# cape.net
KiCad netlist of a schematic drawn in Altium Designer
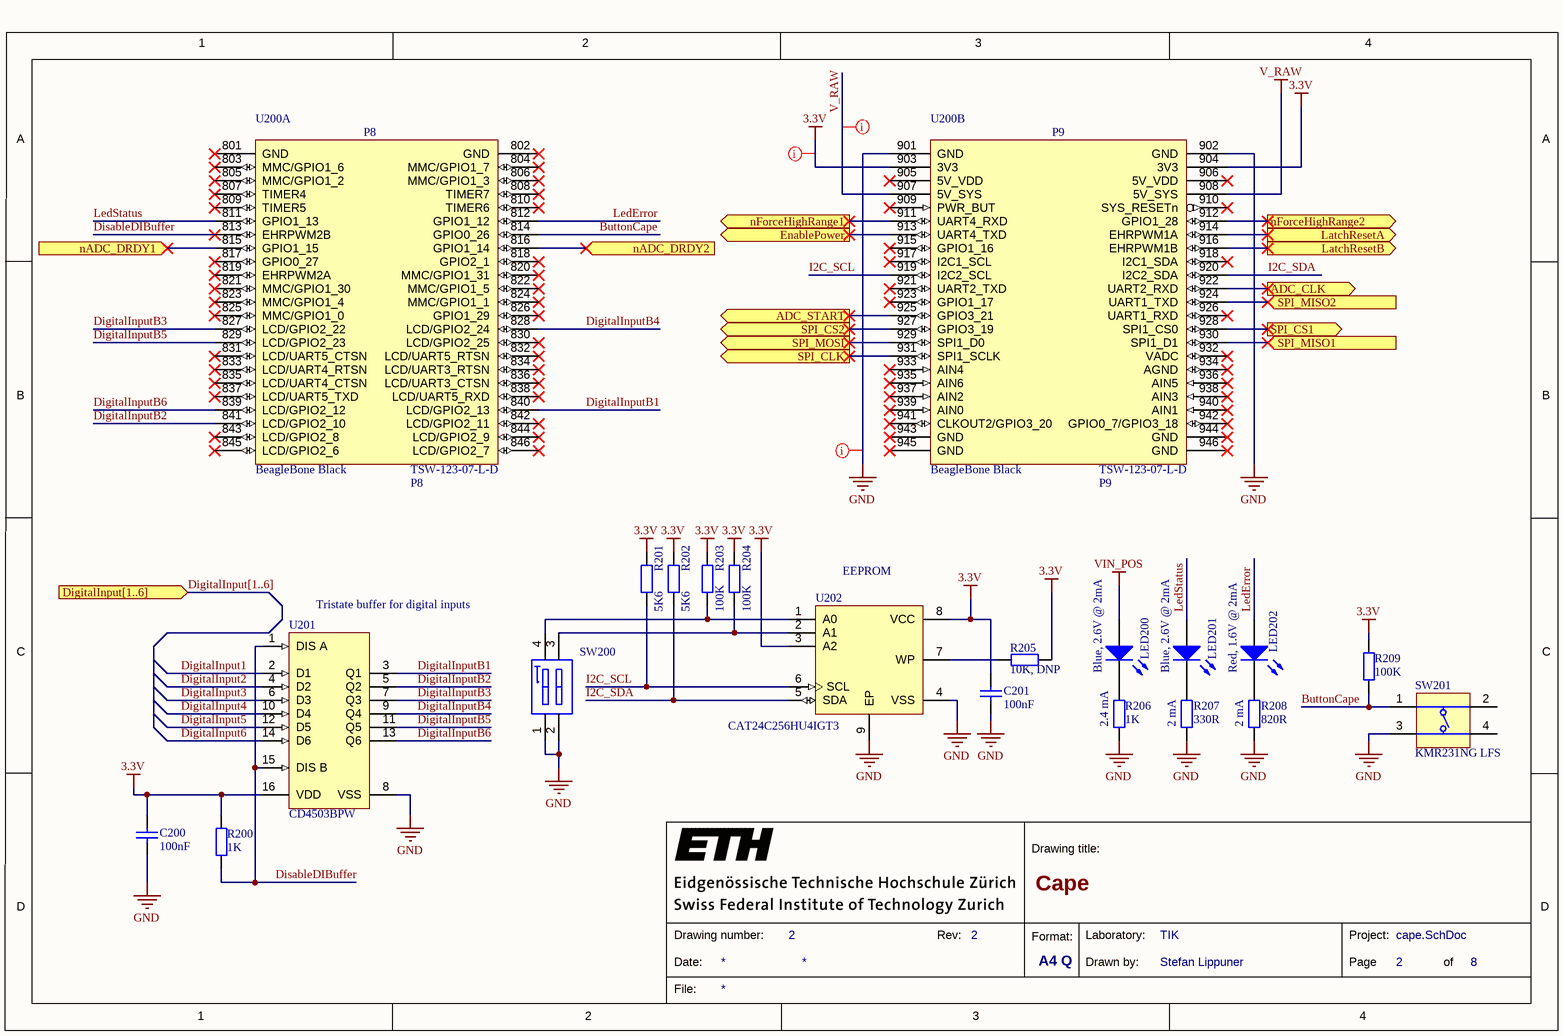
[diagram p0: cape.SchDoc]

(export (version "E")
  (design (tool "Eeschema 10.0.6"))
  (components
    (comp (ref "C200")
      (value "100nF")
      (footprint "CAPC0402(1005)60_L")
      (description "CAP 100nF 16V -20% to +80% 0402 (1005 Metric) Thickness 0.6mm SMD")
      (fields (field (name "TOLERANCE") "-20% to +80%"))
      (libsource (lib "Altium Content Vault") (part "CMP-1034-02071-1"))
    )
    (comp (ref "C201")
      (value "100nF")
      (footprint "CAPC0402(1005)60_L")
      (description "CAP 100nF 16V -20% to +80% 0402 (1005 Metric) Thickness 0.6mm SMD")
      (fields (field (name "TOLERANCE") "-20% to +80%"))
      (libsource (lib "Altium Content Vault") (part "CMP-1034-02071-1"))
    )
    (comp (ref "LED200")
      (value "Blue, 2.6V @ 2mA")
      (footprint "0603_A")
      (description "SMD mono-color Chip LED, WL-SMCW, Blue")
      (fields (field (name "PARTNUMBER") "150060BS75000") (field (name "MANUFACTURER") "Wuerth Elektronik"))
      (libsource (lib "Altium Content Vault") (part "CMP-1426-00003-1"))
    )
    (comp (ref "LED201")
      (value "Blue, 2.6V @ 2mA")
      (footprint "0603_A")
      (description "SMD mono-color Chip LED, WL-SMCW, Blue")
      (fields (field (name "PARTNUMBER") "150060BS75000") (field (name "MANUFACTURER") "Wuerth Elektronik"))
      (libsource (lib "Altium Content Vault") (part "CMP-1426-00003-1"))
    )
    (comp (ref "LED202")
      (value "Red, 1.6V @ 2mA")
      (footprint "0603_A")
      (description "SMD mono-color Chip LED, WL-SMCW, Red")
      (fields (field (name "MANUFACTURER") "Wuerth Elektronik") (field (name "PARTNUMBER") "150060RS75000"))
      (libsource (lib "Altium Content Vault") (part "WE-LED_K1A2-2"))
    )
    (comp (ref "P8")
      (value "TSW-123-07-L-D (BOM)")
      (description "Conn Unshrouded Header HDR 46 POS 2.54mm Solder ST Thru-Hole")
      (libsource (lib "TSW-123-07-L-D") (part "TSW-123-07-L-D (BOM)"))
    )
    (comp (ref "P9")
      (value "TSW-123-07-L-D (BOM)")
      (description "Conn Unshrouded Header HDR 46 POS 2.54mm Solder ST Thru-Hole")
      (libsource (lib "TSW-123-07-L-D") (part "TSW-123-07-L-D (BOM)"))
    )
    (comp (ref "R200")
      (value "1K")
      (footprint "RESC0402(1005)_L")
      (description "1K 0.063W 1% 0402 (1005 Metric)  SMD")
      (fields (field (name "TOLERANCE") "1 %") (field (name "POWER") "0.063 W"))
      (libsource (lib "Altium Content Vault") (part "RES"))
    )
    (comp (ref "R201")
      (value "5K6")
      (footprint "RESC0402(1005)_L")
      (description "5K6 0.063W 5% 0402 (1005 Metric)  SMD")
      (fields (field (name "TOLERANCE") "5 %") (field (name "POWER") "0.063 W"))
      (libsource (lib "Altium Content Vault") (part "CMP-1011-00092-1"))
    )
    (comp (ref "R202")
      (value "5K6")
      (footprint "RESC0402(1005)_L")
      (description "5K6 0.063W 5% 0402 (1005 Metric)  SMD")
      (fields (field (name "TOLERANCE") "5 %") (field (name "POWER") "0.063 W"))
      (libsource (lib "Altium Content Vault") (part "CMP-1011-00092-1"))
    )
    (comp (ref "R203")
      (value "100K")
      (footprint "RESC0402(1005)_L")
      (description "100K 0.063W 1% 0402 (1005 Metric)  SMD")
      (fields (field (name "POWER") "0.063 W") (field (name "TOLERANCE") "1 %"))
      (libsource (lib "Altium Content Vault") (part "CMP-1011-00736"))
    )
    (comp (ref "R204")
      (value "100K")
      (footprint "RESC0402(1005)_L")
      (description "100K 0.063W 1% 0402 (1005 Metric)  SMD")
      (fields (field (name "POWER") "0.063 W") (field (name "TOLERANCE") "1 %"))
      (libsource (lib "Altium Content Vault") (part "CMP-1011-00736"))
    )
    (comp (ref "R205")
      (value "10K, DNP")
      (footprint "RESC0402(1005)_L")
      (description "10K 0.063W 1% 0402 (1005 Metric)  SMD")
      (fields (field (name "TOLERANCE") "1 %") (field (name "POWER") "0.063 W"))
      (libsource (lib "Altium Content Vault") (part "CMP-1011-00623-1"))
    )
    (comp (ref "R206")
      (value "1K")
      (footprint "RESC0402(1005)_L")
      (description "1K 0.063W 1% 0402 (1005 Metric)  SMD")
      (fields (field (name "TOLERANCE") "1 %") (field (name "POWER") "0.063 W"))
      (libsource (lib "Altium Content Vault") (part "RES"))
    )
    (comp (ref "R207")
      (value "330R")
      (footprint "RESC0402(1005)_L")
      (description "330R 0.063W 5% 0402 (1005 Metric)  SMD")
      (fields (field (name "TOLERANCE") "5 %") (field (name "POWER") "0.063 W"))
      (libsource (lib "Altium Content Vault") (part "CMP-1011-00062-1"))
    )
    (comp (ref "R208")
      (value "820R")
      (footprint "RESC0402(1005)_L")
      (description "820R 0.063W 5% 0402 (1005 Metric)  SMD")
      (fields (field (name "TOLERANCE") "5 %") (field (name "POWER") "0.063 W"))
      (libsource (lib "Altium Content Vault") (part "CMP-1011-00072-1"))
    )
    (comp (ref "R209")
      (value "100K")
      (footprint "RESC0402(1005)_L")
      (description "100K 0.063W 1% 0402 (1005 Metric)  SMD")
      (fields (field (name "TOLERANCE") "1 %") (field (name "POWER") "0.063 W"))
      (libsource (lib "Altium Content Vault") (part "CMP-1011-00736"))
    )
    (comp (ref "SW200")
      (value "218-2LPST")
      (footprint "416131160802")
      (description "Switch DIP ON OFF SPST 2 Recessed Slide 0.025A 24VDC Gull Wing 1.27mm SMD")
      (fields (field (name "MANUFACTURER") "CTS Electrocomponents"))
      (libsource (lib "ETHZ Vault") (part "WE-DIP-SW-4"))
    )
    (comp (ref "SW201")
      (value "KMR231NG LFS")
      (footprint "KRM 2 Series")
      (description "SWITCH TACTILE SPST-NO 0.05A 32V")
      (fields (field (name "MANUFACTURER") "C&K Components"))
      (libsource (lib "ETHZ Vault") (part "SW-Push Button"))
    )
    (comp (ref "U200") (value "BeagleBone Black") (libsource (lib "ETHZ Vault") (part "CMP-00111-2")))
    (comp (ref "U201")
      (value "CD4503BPW")
      (footprint "PW0016A_L")
      (description "CMOS Hex Non-Inverting Buffer with 3-State Outputs, PW0016A, TUBE")
      (fields
        (field (name "MANUFACTURER") "Texas Instruments")
        (field (name "GENERIC PART NUMBER") "CD4503B")
      )
      (libsource (lib "Altium Content Vault") (part "TI-CD4503B-16"))
    )
    (comp (ref "U202")
      (value "CAT24C256HU4IGT3")
      (footprint "UDFN-MU8")
      (description "IC EEPROM 256KBIT 400KHZ 8UDFN")
      (fields (field (name "MANUFACTURER") "ON Semiconductor"))
      (libsource (lib "ETHZ Vault") (part "CAT24C256"))
    )
  )
  (nets
    (net (code "1") (name "/ADC_CLK") (class "Default")
      (node (ref "U200") (pin "922") (pinfunction "UART2_RXD_922") (pintype "bidirectional+no_connect"))
    )
    (net (code "2") (name "/ADC_START") (class "Default")
      (node (ref "U200") (pin "925") (pinfunction "GPIO3_21_925") (pintype "bidirectional+no_connect"))
    )
    (net (code "3") (name "/ButtonCape") (class "Default")
      (node (ref "R209") (pin "1") (pinfunction "1_1") (pintype "passive"))
      (node (ref "SW201") (pin "1") (pinfunction "T1_1") (pintype "passive"))
      (node (ref "U200") (pin "814") (pinfunction "GPIO0_26_814") (pintype "bidirectional"))
    )
    (net (code "4") (name "/DigitalInput1") (class "Default")
      (node (ref "U201") (pin "2") (pinfunction "D1_2") (pintype "input"))
    )
    (net (code "5") (name "/DigitalInput2") (class "Default")
      (node (ref "U201") (pin "4") (pinfunction "D2_4") (pintype "input"))
    )
    (net (code "6") (name "/DigitalInput3") (class "Default")
      (node (ref "U201") (pin "6") (pinfunction "D3_6") (pintype "input"))
    )
    (net (code "7") (name "/DigitalInput4") (class "Default")
      (node (ref "U201") (pin "10") (pinfunction "D4_10") (pintype "input"))
    )
    (net (code "8") (name "/DigitalInput5") (class "Default")
      (node (ref "U201") (pin "12") (pinfunction "D5_12") (pintype "input"))
    )
    (net (code "9") (name "/DigitalInput6") (class "Default")
      (node (ref "U201") (pin "14") (pinfunction "D6_14") (pintype "input"))
    )
    (net (code "10") (name "/DigitalInputB1") (class "Default")
      (node (ref "U200") (pin "840") (pinfunction "LCD/GPIO2_13_840") (pintype "bidirectional"))
      (node (ref "U201") (pin "3") (pinfunction "Q1_3") (pintype "tri_state"))
    )
    (net (code "11") (name "/DigitalInputB2") (class "Default")
      (node (ref "U200") (pin "841") (pinfunction "LCD/GPIO2_10_841") (pintype "bidirectional"))
      (node (ref "U201") (pin "5") (pinfunction "Q2_5") (pintype "tri_state"))
    )
    (net (code "12") (name "/DigitalInputB3") (class "Default")
      (node (ref "U200") (pin "827") (pinfunction "LCD/GPIO2_22_827") (pintype "bidirectional"))
      (node (ref "U201") (pin "7") (pinfunction "Q3_7") (pintype "tri_state"))
    )
    (net (code "13") (name "/DigitalInputB4") (class "Default")
      (node (ref "U200") (pin "828") (pinfunction "LCD/GPIO2_24_828") (pintype "bidirectional"))
      (node (ref "U201") (pin "9") (pinfunction "Q4_9") (pintype "tri_state"))
    )
    (net (code "14") (name "/DigitalInputB5") (class "Default")
      (node (ref "U200") (pin "829") (pinfunction "LCD/GPIO2_23_829") (pintype "bidirectional"))
      (node (ref "U201") (pin "11") (pinfunction "Q5_11") (pintype "tri_state"))
    )
    (net (code "15") (name "/DigitalInputB6") (class "Default")
      (node (ref "U200") (pin "839") (pinfunction "LCD/GPIO2_12_839") (pintype "bidirectional"))
      (node (ref "U201") (pin "13") (pinfunction "Q6_13") (pintype "tri_state"))
    )
    (net (code "17") (name "/DisableDIBuffer") (class "Default")
      (node (ref "R200") (pin "1") (pinfunction "1_1") (pintype "passive"))
      (node (ref "U200") (pin "813") (pinfunction "EHRPWM2B_813") (pintype "bidirectional"))
      (node (ref "U201") (pin "1") (pinfunction "DIS_A_1") (pintype "input"))
      (node (ref "U201") (pin "15") (pinfunction "DIS_B_15") (pintype "input"))
    )
    (net (code "18") (name "/EnablePower") (class "Default")
      (node (ref "U200") (pin "913") (pinfunction "UART4_TXD_913") (pintype "bidirectional+no_connect"))
    )
    (net (code "19") (name "/I2C_SCL") (class "Default")
      (node (ref "R201") (pin "1") (pinfunction "1_1") (pintype "passive"))
      (node (ref "U200") (pin "919") (pinfunction "I2C2_SCL_919") (pintype "bidirectional"))
      (node (ref "U202") (pin "6") (pinfunction "SCL_6") (pintype "input"))
    )
    (net (code "20") (name "/I2C_SDA") (class "Default")
      (node (ref "R202") (pin "1") (pinfunction "1_1") (pintype "passive"))
      (node (ref "U200") (pin "920") (pinfunction "I2C2_SDA_920") (pintype "bidirectional"))
      (node (ref "U202") (pin "5") (pinfunction "SDA_5") (pintype "bidirectional"))
    )
    (net (code "21") (name "/LatchResetA") (class "Default")
      (node (ref "U200") (pin "914") (pinfunction "EHRPWM1A_914") (pintype "bidirectional+no_connect"))
    )
    (net (code "22") (name "/LatchResetB") (class "Default")
      (node (ref "U200") (pin "916") (pinfunction "EHRPWM1B_916") (pintype "bidirectional+no_connect"))
    )
    (net (code "23") (name "/LedError") (class "Default")
      (node (ref "LED202") (pin "2") (pinfunction "A_2") (pintype "passive"))
      (node (ref "U200") (pin "812") (pinfunction "GPIO1_12_812") (pintype "bidirectional"))
    )
    (net (code "24") (name "/LedStatus") (class "Default")
      (node (ref "LED201") (pin "2") (pinfunction "A_2") (pintype "passive"))
      (node (ref "U200") (pin "811") (pinfunction "GPIO1_13_811") (pintype "bidirectional"))
    )
    (net (code "25") (name "/SPI_CLK") (class "Default")
      (node (ref "U200") (pin "931") (pinfunction "SPI1_SCLK_931") (pintype "bidirectional+no_connect"))
    )
    (net (code "26") (name "/SPI_CS1") (class "Default")
      (node (ref "U200") (pin "928") (pinfunction "SPI1_CS0_928") (pintype "bidirectional+no_connect"))
    )
    (net (code "27") (name "/SPI_CS2") (class "Default")
      (node (ref "U200") (pin "927") (pinfunction "GPIO3_19_927") (pintype "bidirectional+no_connect"))
    )
    (net (code "28") (name "/SPI_MISO1") (class "Default")
      (node (ref "U200") (pin "930") (pinfunction "SPI1_D1_930") (pintype "bidirectional+no_connect"))
    )
    (net (code "29") (name "/SPI_MISO2") (class "Default")
      (node (ref "U200") (pin "924") (pinfunction "UART1_TXD_924") (pintype "bidirectional+no_connect"))
    )
    (net (code "30") (name "/SPI_MOSI") (class "Default")
      (node (ref "U200") (pin "929") (pinfunction "SPI1_D0_929") (pintype "bidirectional+no_connect"))
    )
    (net (code "31") (name "/nADC_DRDY1") (class "Default")
      (node (ref "U200") (pin "815") (pinfunction "GPIO1_15_815") (pintype "bidirectional+no_connect"))
    )
    (net (code "32") (name "/nADC_DRDY2") (class "Default")
      (node (ref "U200") (pin "816") (pinfunction "GPIO1_14_816") (pintype "bidirectional+no_connect"))
    )
    (net (code "33") (name "/nForceHighRange1") (class "Default")
      (node (ref "U200") (pin "911") (pinfunction "UART4_RXD_911") (pintype "bidirectional+no_connect"))
    )
    (net (code "34") (name "/nForceHighRange2") (class "Default")
      (node (ref "U200") (pin "912") (pinfunction "GPIO1_28_912") (pintype "bidirectional+no_connect"))
    )
    (net (code "35") (name "3.3V") (class "Default")
      (node (ref "C200") (pin "2") (pinfunction "2_2") (pintype "passive"))
      (node (ref "C201") (pin "2") (pinfunction "2_2") (pintype "passive"))
      (node (ref "R200") (pin "2") (pinfunction "2_2") (pintype "passive"))
      (node (ref "R201") (pin "2") (pinfunction "2_2") (pintype "passive"))
      (node (ref "R202") (pin "2") (pinfunction "2_2") (pintype "passive"))
      (node (ref "R203") (pin "2") (pinfunction "2_2") (pintype "passive"))
      (node (ref "R204") (pin "2") (pinfunction "2_2") (pintype "passive"))
      (node (ref "R205") (pin "2") (pinfunction "2_2") (pintype "passive"))
      (node (ref "R209") (pin "2") (pinfunction "2_2") (pintype "passive"))
      (node (ref "U200") (pin "903") (pinfunction "3V3_903") (pintype "power_in"))
      (node (ref "U200") (pin "904") (pinfunction "3V3_904") (pintype "power_in"))
      (node (ref "U201") (pin "16") (pinfunction "VDD_16") (pintype "power_in"))
      (node (ref "U202") (pin "3") (pinfunction "A2_3") (pintype "passive"))
      (node (ref "U202") (pin "8") (pinfunction "VCC_8") (pintype "power_in"))
    )
    (net (code "36") (name "GND") (class "Default")
      (node (ref "C200") (pin "1") (pinfunction "1_1") (pintype "passive"))
      (node (ref "C201") (pin "1") (pinfunction "1_1") (pintype "passive"))
      (node (ref "R206") (pin "1") (pinfunction "1_1") (pintype "passive"))
      (node (ref "R207") (pin "1") (pinfunction "1_1") (pintype "passive"))
      (node (ref "R208") (pin "1") (pinfunction "1_1") (pintype "passive"))
      (node (ref "SW200") (pin "1") (pinfunction "1_1") (pintype "passive"))
      (node (ref "SW200") (pin "2") (pinfunction "2_2") (pintype "passive"))
      (node (ref "SW201") (pin "3") (pinfunction "T3_3") (pintype "passive"))
      (node (ref "U200") (pin "901") (pinfunction "GND_901") (pintype "passive"))
      (node (ref "U200") (pin "902") (pinfunction "GND_902") (pintype "passive"))
      (node (ref "U201") (pin "8") (pinfunction "VSS_8") (pintype "power_in"))
      (node (ref "U202") (pin "4") (pinfunction "VSS_4") (pintype "power_in"))
      (node (ref "U202") (pin "9") (pinfunction "EP_9") (pintype "power_in"))
    )
    (net (code "37") (name "Net-(LED200-K)") (class "Default")
      (node (ref "LED200") (pin "1") (pinfunction "K_1") (pintype "passive"))
      (node (ref "R206") (pin "2") (pinfunction "2_2") (pintype "passive"))
    )
    (net (code "38") (name "Net-(LED201-K)") (class "Default")
      (node (ref "LED201") (pin "1") (pinfunction "K_1") (pintype "passive"))
      (node (ref "R207") (pin "2") (pinfunction "2_2") (pintype "passive"))
    )
    (net (code "39") (name "Net-(LED202-K)") (class "Default")
      (node (ref "LED202") (pin "1") (pinfunction "K_1") (pintype "passive"))
      (node (ref "R208") (pin "2") (pinfunction "2_2") (pintype "passive"))
    )
    (net (code "40") (name "Net-(U202-A0)") (class "Default")
      (node (ref "R203") (pin "1") (pinfunction "1_1") (pintype "passive"))
      (node (ref "SW200") (pin "4") (pinfunction "4_4") (pintype "passive"))
      (node (ref "U202") (pin "1") (pinfunction "A0_1") (pintype "passive"))
    )
    (net (code "41") (name "Net-(U202-A1)") (class "Default")
      (node (ref "R204") (pin "1") (pinfunction "1_1") (pintype "passive"))
      (node (ref "SW200") (pin "3") (pinfunction "3_3") (pintype "passive"))
      (node (ref "U202") (pin "2") (pinfunction "A1_2") (pintype "passive"))
    )
    (net (code "42") (name "Net-(U202-WP)") (class "Default")
      (node (ref "R205") (pin "1") (pinfunction "1_1") (pintype "passive"))
      (node (ref "U202") (pin "7") (pinfunction "WP_7") (pintype "passive"))
    )
    (net (code "43") (name "VIN_POS") (class "Default")
      (node (ref "LED200") (pin "2") (pinfunction "A_2") (pintype "passive"))
    )
    (net (code "44") (name "V_RAW") (class "Default")
      (node (ref "U200") (pin "907") (pinfunction "5V_SYS_907") (pintype "power_in"))
      (node (ref "U200") (pin "908") (pinfunction "5V_SYS_908") (pintype "power_in"))
    )
    (net (code "45") (name "unconnected-(SW201-T2-Pad2)") (class "Default")
      (node (ref "SW201") (pin "2") (pinfunction "T2_2") (pintype "passive"))
    )
    (net (code "46") (name "unconnected-(SW201-T3-Pad4)") (class "Default")
      (node (ref "SW201") (pin "4") (pinfunction "T3_4") (pintype "passive"))
    )
    (net (code "47") (name "unconnected-(U200A-EHRPWM2A-Pad819)") (class "Default")
      (node (ref "U200") (pin "819") (pinfunction "EHRPWM2A_819") (pintype "bidirectional+no_connect"))
    )
    (net (code "48") (name "unconnected-(U200A-GND-Pad801)") (class "Default")
      (node (ref "U200") (pin "801") (pinfunction "GND_801") (pintype "power_in+no_connect"))
    )
    (net (code "49") (name "unconnected-(U200A-GND-Pad802)") (class "Default")
      (node (ref "U200") (pin "802") (pinfunction "GND_802") (pintype "power_in+no_connect"))
    )
    (net (code "50") (name "unconnected-(U200A-GPIO0_27-Pad817)") (class "Default")
      (node (ref "U200") (pin "817") (pinfunction "GPIO0_27_817") (pintype "bidirectional+no_connect"))
    )
    (net (code "51") (name "unconnected-(U200A-GPIO1_29-Pad826)") (class "Default")
      (node (ref "U200") (pin "826") (pinfunction "GPIO1_29_826") (pintype "bidirectional+no_connect"))
    )
    (net (code "52") (name "unconnected-(U200A-GPIO2_1-Pad818)") (class "Default")
      (node (ref "U200") (pin "818") (pinfunction "GPIO2_1_818") (pintype "bidirectional+no_connect"))
    )
    (net (code "53") (name "unconnected-(U200A-LCD{slash}GPIO2_6-Pad845)") (class "Default")
      (node (ref "U200") (pin "845") (pinfunction "LCD/GPIO2_6_845") (pintype "bidirectional+no_connect"))
    )
    (net (code "54") (name "unconnected-(U200A-LCD{slash}GPIO2_7-Pad846)") (class "Default")
      (node (ref "U200") (pin "846") (pinfunction "LCD/GPIO2_7_846") (pintype "bidirectional+no_connect"))
    )
    (net (code "55") (name "unconnected-(U200A-LCD{slash}GPIO2_8-Pad843)") (class "Default")
      (node (ref "U200") (pin "843") (pinfunction "LCD/GPIO2_8_843") (pintype "bidirectional+no_connect"))
    )
    (net (code "56") (name "unconnected-(U200A-LCD{slash}GPIO2_9-Pad844)") (class "Default")
      (node (ref "U200") (pin "844") (pinfunction "LCD/GPIO2_9_844") (pintype "bidirectional+no_connect"))
    )
    (net (code "57") (name "unconnected-(U200A-LCD{slash}GPIO2_11-Pad842)") (class "Default")
      (node (ref "U200") (pin "842") (pinfunction "LCD/GPIO2_11_842") (pintype "bidirectional+no_connect"))
    )
    (net (code "58") (name "unconnected-(U200A-LCD{slash}GPIO2_25-Pad830)") (class "Default")
      (node (ref "U200") (pin "830") (pinfunction "LCD/GPIO2_25_830") (pintype "bidirectional+no_connect"))
    )
    (net (code "59") (name "unconnected-(U200A-LCD{slash}UART3_CTSN-Pad836)") (class "Default")
      (node (ref "U200") (pin "836") (pinfunction "LCD/UART3_CTSN_836") (pintype "bidirectional+no_connect"))
    )
    (net (code "60") (name "unconnected-(U200A-LCD{slash}UART3_RTSN-Pad834)") (class "Default")
      (node (ref "U200") (pin "834") (pinfunction "LCD/UART3_RTSN_834") (pintype "bidirectional+no_connect"))
    )
    (net (code "61") (name "unconnected-(U200A-LCD{slash}UART4_CTSN-Pad835)") (class "Default")
      (node (ref "U200") (pin "835") (pinfunction "LCD/UART4_CTSN_835") (pintype "bidirectional+no_connect"))
    )
    (net (code "62") (name "unconnected-(U200A-LCD{slash}UART4_RTSN-Pad833)") (class "Default")
      (node (ref "U200") (pin "833") (pinfunction "LCD/UART4_RTSN_833") (pintype "bidirectional+no_connect"))
    )
    (net (code "63") (name "unconnected-(U200A-LCD{slash}UART5_CTSN-Pad831)") (class "Default")
      (node (ref "U200") (pin "831") (pinfunction "LCD/UART5_CTSN_831") (pintype "bidirectional+no_connect"))
    )
    (net (code "64") (name "unconnected-(U200A-LCD{slash}UART5_RTSN-Pad832)") (class "Default")
      (node (ref "U200") (pin "832") (pinfunction "LCD/UART5_RTSN_832") (pintype "bidirectional+no_connect"))
    )
    (net (code "65") (name "unconnected-(U200A-LCD{slash}UART5_RXD-Pad838)") (class "Default")
      (node (ref "U200") (pin "838") (pinfunction "LCD/UART5_RXD_838") (pintype "bidirectional+no_connect"))
    )
    (net (code "66") (name "unconnected-(U200A-LCD{slash}UART5_TXD-Pad837)") (class "Default")
      (node (ref "U200") (pin "837") (pinfunction "LCD/UART5_TXD_837") (pintype "bidirectional+no_connect"))
    )
    (net (code "67") (name "unconnected-(U200A-MMC{slash}GPIO1_0-Pad825)") (class "Default")
      (node (ref "U200") (pin "825") (pinfunction "MMC/GPIO1_0_825") (pintype "bidirectional+no_connect"))
    )
    (net (code "68") (name "unconnected-(U200A-MMC{slash}GPIO1_1-Pad824)") (class "Default")
      (node (ref "U200") (pin "824") (pinfunction "MMC/GPIO1_1_824") (pintype "bidirectional+no_connect"))
    )
    (net (code "69") (name "unconnected-(U200A-MMC{slash}GPIO1_2-Pad805)") (class "Default")
      (node (ref "U200") (pin "805") (pinfunction "MMC/GPIO1_2_805") (pintype "bidirectional+no_connect"))
    )
    (net (code "70") (name "unconnected-(U200A-MMC{slash}GPIO1_3-Pad806)") (class "Default")
      (node (ref "U200") (pin "806") (pinfunction "MMC/GPIO1_3_806") (pintype "bidirectional+no_connect"))
    )
    (net (code "71") (name "unconnected-(U200A-MMC{slash}GPIO1_4-Pad823)") (class "Default")
      (node (ref "U200") (pin "823") (pinfunction "MMC/GPIO1_4_823") (pintype "bidirectional+no_connect"))
    )
    (net (code "72") (name "unconnected-(U200A-MMC{slash}GPIO1_5-Pad822)") (class "Default")
      (node (ref "U200") (pin "822") (pinfunction "MMC/GPIO1_5_822") (pintype "bidirectional+no_connect"))
    )
    (net (code "73") (name "unconnected-(U200A-MMC{slash}GPIO1_6-Pad803)") (class "Default")
      (node (ref "U200") (pin "803") (pinfunction "MMC/GPIO1_6_803") (pintype "bidirectional+no_connect"))
    )
    (net (code "74") (name "unconnected-(U200A-MMC{slash}GPIO1_7-Pad804)") (class "Default")
      (node (ref "U200") (pin "804") (pinfunction "MMC/GPIO1_7_804") (pintype "bidirectional+no_connect"))
    )
    (net (code "75") (name "unconnected-(U200A-MMC{slash}GPIO1_30-Pad821)") (class "Default")
      (node (ref "U200") (pin "821") (pinfunction "MMC/GPIO1_30_821") (pintype "bidirectional+no_connect"))
    )
    (net (code "76") (name "unconnected-(U200A-MMC{slash}GPIO1_31-Pad820)") (class "Default")
      (node (ref "U200") (pin "820") (pinfunction "MMC/GPIO1_31_820") (pintype "bidirectional+no_connect"))
    )
    (net (code "77") (name "unconnected-(U200A-TIMER4-Pad807)") (class "Default")
      (node (ref "U200") (pin "807") (pinfunction "TIMER4_807") (pintype "bidirectional+no_connect"))
    )
    (net (code "78") (name "unconnected-(U200A-TIMER5-Pad809)") (class "Default")
      (node (ref "U200") (pin "809") (pinfunction "TIMER5_809") (pintype "bidirectional+no_connect"))
    )
    (net (code "79") (name "unconnected-(U200A-TIMER6-Pad810)") (class "Default")
      (node (ref "U200") (pin "810") (pinfunction "TIMER6_810") (pintype "bidirectional+no_connect"))
    )
    (net (code "80") (name "unconnected-(U200A-TIMER7-Pad808)") (class "Default")
      (node (ref "U200") (pin "808") (pinfunction "TIMER7_808") (pintype "bidirectional+no_connect"))
    )
    (net (code "81") (name "unconnected-(U200B-5V_VDD-Pad905)") (class "Default")
      (node (ref "U200") (pin "905") (pinfunction "5V_VDD_905") (pintype "power_in+no_connect"))
    )
    (net (code "82") (name "unconnected-(U200B-5V_VDD-Pad906)") (class "Default")
      (node (ref "U200") (pin "906") (pinfunction "5V_VDD_906") (pintype "power_in+no_connect"))
    )
    (net (code "83") (name "unconnected-(U200B-AGND-Pad934)") (class "Default")
      (node (ref "U200") (pin "934") (pinfunction "AGND_934") (pintype "bidirectional+no_connect"))
    )
    (net (code "84") (name "unconnected-(U200B-AIN0-Pad939)") (class "Default")
      (node (ref "U200") (pin "939") (pinfunction "AIN0_939") (pintype "input+no_connect"))
    )
    (net (code "85") (name "unconnected-(U200B-AIN1-Pad940)") (class "Default")
      (node (ref "U200") (pin "940") (pinfunction "AIN1_940") (pintype "input+no_connect"))
    )
    (net (code "86") (name "unconnected-(U200B-AIN2-Pad937)") (class "Default")
      (node (ref "U200") (pin "937") (pinfunction "AIN2_937") (pintype "input+no_connect"))
    )
    (net (code "87") (name "unconnected-(U200B-AIN3-Pad938)") (class "Default")
      (node (ref "U200") (pin "938") (pinfunction "AIN3_938") (pintype "input+no_connect"))
    )
    (net (code "88") (name "unconnected-(U200B-AIN4-Pad933)") (class "Default")
      (node (ref "U200") (pin "933") (pinfunction "AIN4_933") (pintype "input+no_connect"))
    )
    (net (code "89") (name "unconnected-(U200B-AIN5-Pad936)") (class "Default")
      (node (ref "U200") (pin "936") (pinfunction "AIN5_936") (pintype "input+no_connect"))
    )
    (net (code "90") (name "unconnected-(U200B-AIN6-Pad935)") (class "Default")
      (node (ref "U200") (pin "935") (pinfunction "AIN6_935") (pintype "input+no_connect"))
    )
    (net (code "91") (name "unconnected-(U200B-CLKOUT2{slash}GPIO3_20-Pad941)") (class "Default")
      (node (ref "U200") (pin "941") (pinfunction "CLKOUT2/GPIO3_20_941") (pintype "bidirectional+no_connect"))
    )
    (net (code "92") (name "unconnected-(U200B-GND-Pad943)") (class "Default")
      (node (ref "U200") (pin "943") (pinfunction "GND_943") (pintype "power_in+no_connect"))
    )
    (net (code "93") (name "unconnected-(U200B-GND-Pad944)") (class "Default")
      (node (ref "U200") (pin "944") (pinfunction "GND_944") (pintype "power_in+no_connect"))
    )
    (net (code "94") (name "unconnected-(U200B-GND-Pad945)") (class "Default")
      (node (ref "U200") (pin "945") (pinfunction "GND_945") (pintype "power_in+no_connect"))
    )
    (net (code "95") (name "unconnected-(U200B-GND-Pad946)") (class "Default")
      (node (ref "U200") (pin "946") (pinfunction "GND_946") (pintype "power_in+no_connect"))
    )
    (net (code "96") (name "unconnected-(U200B-GPIO0_7{slash}GPIO3_18-Pad942)") (class "Default")
      (node (ref "U200") (pin "942") (pinfunction "GPIO0_7/GPIO3_18_942") (pintype "bidirectional+no_connect"))
    )
    (net (code "97") (name "unconnected-(U200B-GPIO1_16-Pad915)") (class "Default")
      (node (ref "U200") (pin "915") (pinfunction "GPIO1_16_915") (pintype "bidirectional+no_connect"))
    )
    (net (code "98") (name "unconnected-(U200B-GPIO1_17-Pad923)") (class "Default")
      (node (ref "U200") (pin "923") (pinfunction "GPIO1_17_923") (pintype "bidirectional+no_connect"))
    )
    (net (code "99") (name "unconnected-(U200B-I2C1_SCL-Pad917)") (class "Default")
      (node (ref "U200") (pin "917") (pinfunction "I2C1_SCL_917") (pintype "bidirectional+no_connect"))
    )
    (net (code "100") (name "unconnected-(U200B-I2C1_SDA-Pad918)") (class "Default")
      (node (ref "U200") (pin "918") (pinfunction "I2C1_SDA_918") (pintype "bidirectional+no_connect"))
    )
    (net (code "101") (name "unconnected-(U200B-PWR_BUT-Pad909)") (class "Default")
      (node (ref "U200") (pin "909") (pinfunction "PWR_BUT_909") (pintype "input+no_connect"))
    )
    (net (code "102") (name "unconnected-(U200B-SYS_RESETn-Pad910)") (class "Default")
      (node (ref "U200") (pin "910") (pinfunction "SYS_RESETn_910") (pintype "output+no_connect"))
    )
    (net (code "103") (name "unconnected-(U200B-UART1_RXD-Pad926)") (class "Default")
      (node (ref "U200") (pin "926") (pinfunction "UART1_RXD_926") (pintype "bidirectional+no_connect"))
    )
    (net (code "104") (name "unconnected-(U200B-UART2_TXD-Pad921)") (class "Default")
      (node (ref "U200") (pin "921") (pinfunction "UART2_TXD_921") (pintype "bidirectional+no_connect"))
    )
    (net (code "105") (name "unconnected-(U200B-VADC-Pad932)") (class "Default")
      (node (ref "U200") (pin "932") (pinfunction "VADC_932") (pintype "bidirectional+no_connect"))
    )
  )
)
